# EEPROM.net
KiCad netlist of a schematic drawn in Altium Designer
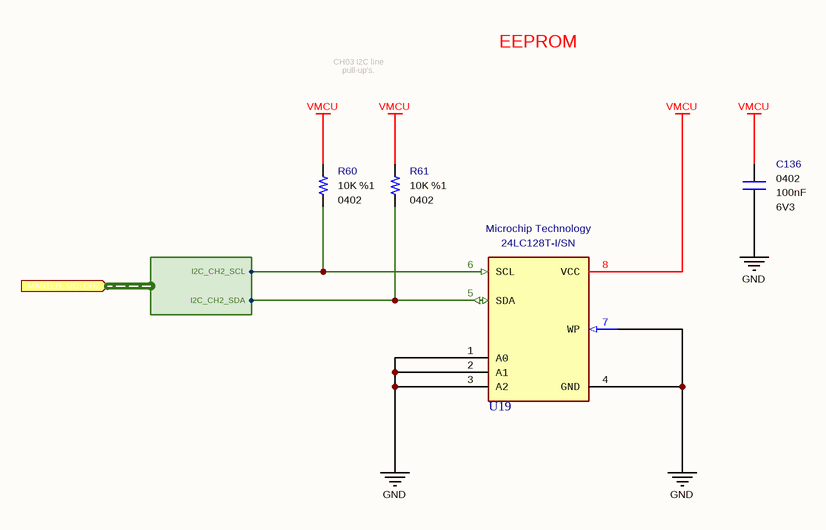
[diagram p0: EEPROM.SchDoc]

(export (version "E")
  (design (tool "Eeschema 10.0.6"))
  (components
    (comp (ref "C136")
      (value "100nF")
      (footprint "CAPACITOR_0402")
      (description "Capacitor - 100nF [0402-6V3] (Ceramic)")
      (fields
        (field (name "TOLERANCE") "%10")
        (field (name "CASE") "0402")
        (field (name "VOLTAGE") "6V3")
        (field (name "MANUFACTURER PART NUMBER") "04026D104KAT4A")
      )
      (libsource (lib "Ovoo_Library") (part "Capacitor - 100nF [0402-6V3]"))
    )
    (comp (ref "R60")
      (value "10K")
      (footprint "RESISTOR_0402")
      (description "Thick Film Resistors - SMD 1/16 W 10 Kohms 1%")
      (fields
        (field (name "TOLERANCE") "%1")
        (field (name "CASE") "0402")
        (field (name "MANUFACTURER PART NUMBER") "CRCW040210K0FKED")
        (field (name "MOUSER PART NUMBER") "71-CRCW0402-10K-E3")
      )
      (libsource (lib "Ovoo_Library") (part "Resistor - 10K"))
    )
    (comp (ref "R61")
      (value "10K")
      (footprint "RESISTOR_0402")
      (description "Thick Film Resistors - SMD 1/16 W 10 Kohms 1%")
      (fields
        (field (name "TOLERANCE") "%1")
        (field (name "CASE") "0402")
        (field (name "MANUFACTURER PART NUMBER") "CRCW040210K0FKED")
        (field (name "MOUSER PART NUMBER") "71-CRCW0402-10K-E3")
      )
      (libsource (lib "Ovoo_Library") (part "Resistor - 10K"))
    )
    (comp (ref "U19")
      (value "EEPROM")
      (footprint "SOIC-8")
      (fields
        (field (name "MANUFACTURER PART NUMBER") "24LC128T-I/SN")
        (field (name "MANUFACTURER NAME") "Microchip Technology")
        (field (name "MOUSER PART NUMBER") "579-24LC128T-I/SN")
      )
      (libsource (lib "Ovoo_Library") (part "IC - 24LC128"))
    )
  )
  (nets
    (net (code "3") (name "GND") (class "Default")
      (node (ref "C136") (pin "1") (pinfunction "1_1") (pintype "passive"))
      (node (ref "U19") (pin "1") (pinfunction "A0_1") (pintype "passive"))
      (node (ref "U19") (pin "2") (pinfunction "A1_2") (pintype "passive"))
      (node (ref "U19") (pin "3") (pinfunction "A2_3") (pintype "passive"))
      (node (ref "U19") (pin "4") (pinfunction "GND_4") (pintype "passive"))
      (node (ref "U19") (pin "7") (pinfunction "WP_7") (pintype "input"))
    )
    (net (code "4") (name "Net-(U19-SCL)") (class "Default")
      (node (ref "R60") (pin "1") (pinfunction "1_1") (pintype "passive"))
      (node (ref "U19") (pin "6") (pinfunction "SCL_6") (pintype "input"))
    )
    (net (code "5") (name "Net-(U19-SDA)") (class "Default")
      (node (ref "R61") (pin "1") (pinfunction "1_1") (pintype "passive"))
      (node (ref "U19") (pin "5") (pinfunction "SDA_5") (pintype "bidirectional"))
    )
    (net (code "6") (name "VMCU") (class "Default")
      (node (ref "C136") (pin "2") (pinfunction "2_2") (pintype "passive"))
      (node (ref "R60") (pin "2") (pinfunction "2_2") (pintype "passive"))
      (node (ref "R61") (pin "2") (pinfunction "2_2") (pintype "passive"))
      (node (ref "U19") (pin "8") (pinfunction "VCC_8") (pintype "power_in"))
    )
  )
)
